# RG3205W-EDLer.net
KiCad netlist of a schematic drawn in EasyEDA Pro
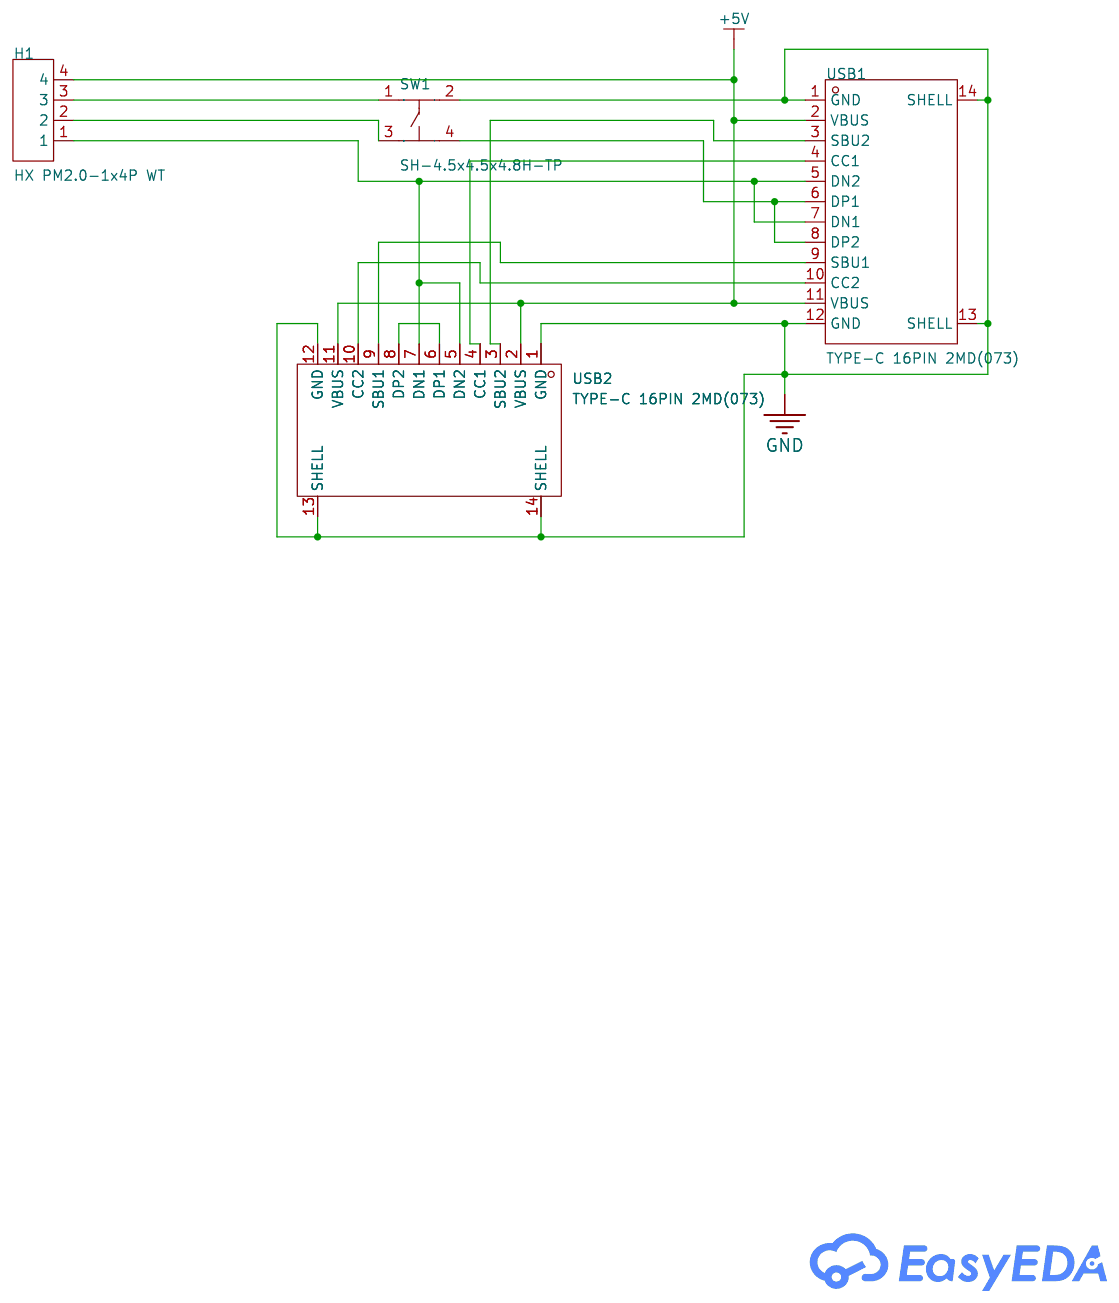
[diagram p0: schematic sheet]

(export (version "E")
  (design (tool "Eeschema 10.0.6"))
  (components
    (comp (ref "H1")
      (value "HX PM2.0-1x4P WT")
      (footprint "easyedapro:HDR-SMD_4P-P2.00_HXPM2.0-1X4PWT")
      (fields (field (name "Manufacturer") "hanxia(韩下)"))
      (libsource (lib "easyedapro") (part "HX PM2.0-1X4P WT"))
    )
    (comp (ref "SW1")
      (value "SH-4.5x4.5x4.8H-TP")
      (footprint "easyedapro:SW-SMD_4P-L4.5-W4.5-P3.00-LS6.9")
      (fields (field (name "Manufacturer") "SHOU HAN(首韩)"))
      (libsource (lib "easyedapro") (part "SH-4.5X4.5X4.8H-TP"))
    )
    (comp (ref "USB1")
      (value "TYPE-C 16PIN 2MD(073)")
      (footprint "easyedapro:USB-C-SMD_TYPE-C-6PIN-2MD-073")
      (fields (field (name "Manufacturer") "SHOU HAN(首韩)"))
      (libsource (lib "easyedapro") (part "TYPE-C 16PIN 2MD(073)"))
    )
    (comp (ref "USB2")
      (value "TYPE-C 16PIN 2MD(073)")
      (footprint "easyedapro:USB-C-SMD_TYPE-C-6PIN-2MD-073")
      (fields (field (name "Manufacturer") "SHOU HAN(首韩)"))
      (libsource (lib "easyedapro") (part "TYPE-C 16PIN 2MD(073)"))
    )
  )
  (nets
    (net (code "1") (name "+5V") (class "Default")
      (node (ref "H1") (pin "4") (pinfunction "4_4") (pintype "unspecified"))
      (node (ref "USB1") (pin "11") (pinfunction "VBUS_11") (pintype "unspecified"))
      (node (ref "USB1") (pin "2") (pinfunction "VBUS_2") (pintype "unspecified"))
      (node (ref "USB2") (pin "11") (pinfunction "VBUS_11") (pintype "unspecified"))
      (node (ref "USB2") (pin "2") (pinfunction "VBUS_2") (pintype "unspecified"))
    )
    (net (code "2") (name "GND") (class "Default")
      (node (ref "SW1") (pin "2") (pinfunction "2_2") (pintype "unspecified"))
      (node (ref "USB1") (pin "1") (pinfunction "GND_1") (pintype "unspecified"))
      (node (ref "USB1") (pin "12") (pinfunction "GND_12") (pintype "unspecified"))
      (node (ref "USB1") (pin "13") (pinfunction "SHELL_13") (pintype "unspecified"))
      (node (ref "USB1") (pin "14") (pinfunction "SHELL_14") (pintype "unspecified"))
      (node (ref "USB2") (pin "1") (pinfunction "GND_1") (pintype "unspecified"))
      (node (ref "USB2") (pin "12") (pinfunction "GND_12") (pintype "unspecified"))
      (node (ref "USB2") (pin "13") (pinfunction "SHELL_13") (pintype "unspecified"))
      (node (ref "USB2") (pin "14") (pinfunction "SHELL_14") (pintype "unspecified"))
    )
    (net (code "3") (name "Net-(H1-Pad2)") (class "Default")
      (node (ref "H1") (pin "2") (pinfunction "2_2") (pintype "unspecified"))
      (node (ref "SW1") (pin "3") (pinfunction "3_3") (pintype "unspecified"))
    )
    (net (code "4") (name "Net-(H1-Pad3)") (class "Default")
      (node (ref "H1") (pin "3") (pinfunction "3_3") (pintype "unspecified"))
      (node (ref "SW1") (pin "1") (pinfunction "1_1") (pintype "unspecified"))
    )
    (net (code "5") (name "Net-(USB1-CC1)") (class "Default")
      (node (ref "USB1") (pin "4") (pinfunction "CC1_4") (pintype "unspecified"))
      (node (ref "USB2") (pin "4") (pinfunction "CC1_4") (pintype "unspecified"))
    )
    (net (code "6") (name "Net-(USB1-CC2)") (class "Default")
      (node (ref "USB1") (pin "10") (pinfunction "CC2_10") (pintype "unspecified"))
      (node (ref "USB2") (pin "10") (pinfunction "CC2_10") (pintype "unspecified"))
    )
    (net (code "7") (name "Net-(USB1-DN1)") (class "Default")
      (node (ref "H1") (pin "1") (pinfunction "1_1") (pintype "unspecified"))
      (node (ref "USB1") (pin "5") (pinfunction "DN2_5") (pintype "unspecified"))
      (node (ref "USB1") (pin "7") (pinfunction "DN1_7") (pintype "unspecified"))
      (node (ref "USB2") (pin "5") (pinfunction "DN2_5") (pintype "unspecified"))
      (node (ref "USB2") (pin "7") (pinfunction "DN1_7") (pintype "unspecified"))
    )
    (net (code "8") (name "Net-(USB1-DP1)") (class "Default")
      (node (ref "SW1") (pin "4") (pinfunction "4_4") (pintype "unspecified"))
      (node (ref "USB1") (pin "6") (pinfunction "DP1_6") (pintype "unspecified"))
      (node (ref "USB1") (pin "8") (pinfunction "DP2_8") (pintype "unspecified"))
    )
    (net (code "9") (name "Net-(USB1-SBU1)") (class "Default")
      (node (ref "USB1") (pin "9") (pinfunction "SBU1_9") (pintype "unspecified"))
      (node (ref "USB2") (pin "9") (pinfunction "SBU1_9") (pintype "unspecified"))
    )
    (net (code "10") (name "Net-(USB1-SBU2)") (class "Default")
      (node (ref "USB1") (pin "3") (pinfunction "SBU2_3") (pintype "unspecified"))
      (node (ref "USB2") (pin "3") (pinfunction "SBU2_3") (pintype "unspecified"))
    )
    (net (code "11") (name "Net-(USB2-DP1)") (class "Default")
      (node (ref "USB2") (pin "6") (pinfunction "DP1_6") (pintype "unspecified"))
      (node (ref "USB2") (pin "8") (pinfunction "DP2_8") (pintype "unspecified"))
    )
  )
)
